# DisplayReceiver_Perpiph.net
KiCad netlist of a schematic drawn in Altium Designer
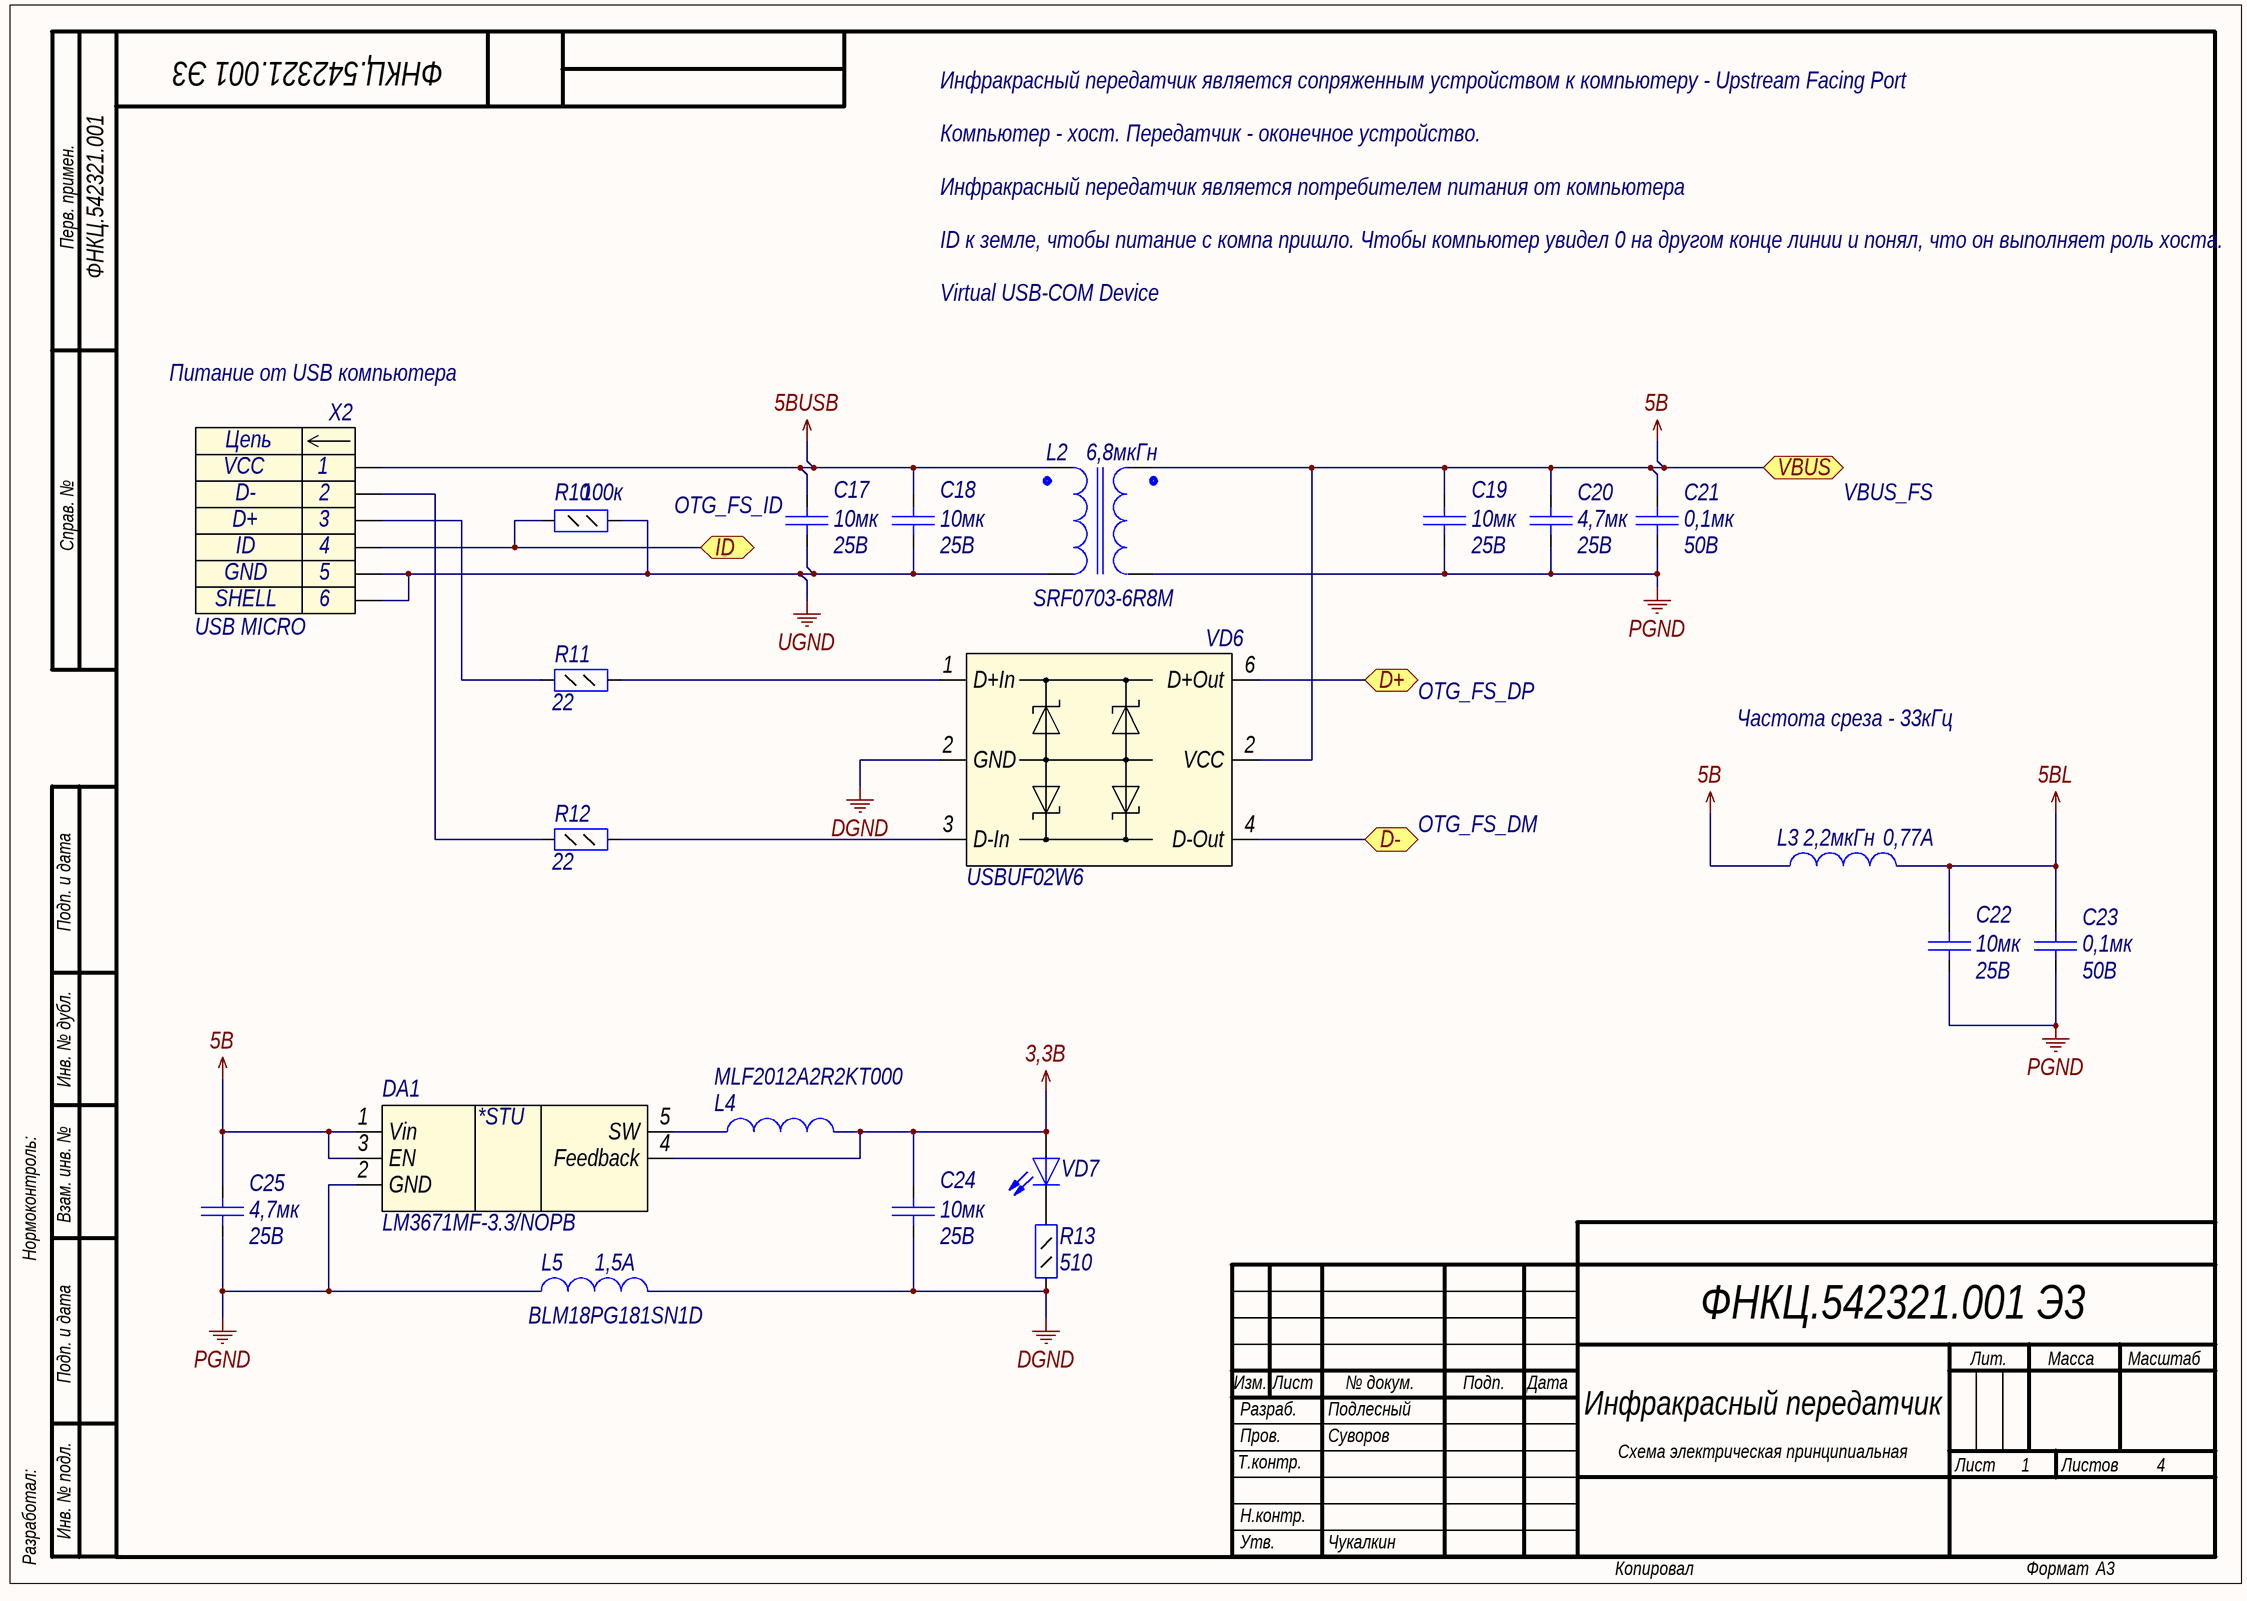
[diagram p0: DisplayReceiver_Perpiph.SchDoc]

(export (version "E")
  (design (tool "Eeschema 10.0.6"))
  (components
    (comp (ref "C17")
      (value "10мк")
      (footprint "C1206")
      (description "Конденсатор")
      (fields
        (field (name "VOLTAGE") "25В")
        (field (name "PART NUMBER") "GRM31CR71E106KA12L*")
        (field (name "Comment") "Capacitor")
      )
      (libsource (lib "MOP44") (part "Capacitor"))
    )
    (comp (ref "C18")
      (value "10мк")
      (footprint "C1206")
      (description "Конденсатор")
      (fields
        (field (name "VOLTAGE") "25В")
        (field (name "PART NUMBER") "GRM31CR71E106KA12L*")
        (field (name "Comment") "Capacitor")
      )
      (libsource (lib "MOP44") (part "Capacitor"))
    )
    (comp (ref "C19")
      (value "10мк")
      (footprint "C1206")
      (description "Конденсатор")
      (fields
        (field (name "VOLTAGE") "25В")
        (field (name "PART NUMBER") "GRM31CR71E106KA12L*")
        (field (name "Comment") "Capacitor")
      )
      (libsource (lib "MOP44") (part "Capacitor"))
    )
    (comp (ref "C20")
      (value "4,7мк")
      (footprint "C0805")
      (description "Конденсатор")
      (fields
        (field (name "VOLTAGE") "25B")
        (field (name "PART NUMBER") "GRM21BR61E475KA12L")
        (field (name "Comment") "Capacitor")
      )
      (libsource (lib "MOP44") (part "Capacitor"))
    )
    (comp (ref "C21")
      (value "0,1мк")
      (footprint "C0805")
      (description "Конденсатор")
      (fields
        (field (name "VOLTAGE") "50B")
        (field (name "PART NUMBER") "GRM21BR71H104K**")
        (field (name "Comment") "Capacitor")
      )
      (libsource (lib "MOP44") (part "Capacitor"))
    )
    (comp (ref "C22")
      (value "10мк")
      (footprint "C1206")
      (description "Конденсатор")
      (fields
        (field (name "VOLTAGE") "25В")
        (field (name "PART NUMBER") "GRM31CR71E106KA12L*")
        (field (name "Comment") "Capacitor")
      )
      (libsource (lib "MOP44") (part "Capacitor"))
    )
    (comp (ref "C23")
      (value "0,1мк")
      (footprint "C0805")
      (description "Конденсатор")
      (fields
        (field (name "VOLTAGE") "50B")
        (field (name "PART NUMBER") "GRM21BR71H104K**")
        (field (name "Comment") "Capacitor")
      )
      (libsource (lib "MOP44") (part "Capacitor"))
    )
    (comp (ref "C24")
      (value "10мк")
      (footprint "C1206")
      (description "Конденсатор")
      (fields
        (field (name "VOLTAGE") "25В")
        (field (name "PART NUMBER") "GRM31CR71E106KA12L*")
        (field (name "Comment") "Capacitor")
      )
      (libsource (lib "MOP44") (part "Capacitor"))
    )
    (comp (ref "C25")
      (value "4,7мк")
      (footprint "C0805")
      (description "Конденсатор")
      (fields
        (field (name "VOLTAGE") "25B")
        (field (name "PART NUMBER") "GRM21BR61E475KA12L")
        (field (name "Comment") "Capacitor")
      )
      (libsource (lib "MOP44") (part "Capacitor"))
    )
    (comp (ref "DA1")
      (value "LM3671MF-3.3/NOPB")
      (footprint "SOT23-5")
      (description "Step-Down DC-DC Converter")
      (fields (field (name "MANUFACTURER") "Texas Instruments"))
      (libsource (lib "MOP44") (part "LM3671MF-3.3/NOPB"))
    )
    (comp (ref "L2")
      (value "6,8мкГн")
      (footprint "SRF0703")
      (description "Синфазный дроссель")
      (fields (field (name "PART NUMBER") "SRF0703-6R8M") (field (name "Comment") "Dual-Winding Inductor"))
      (libsource (lib "MOP44") (part "Dual-Winding Inductor"))
    )
    (comp (ref "L3")
      (value "2,2мкГн")
      (footprint "L1210")
      (description "EMI Suppression Filter")
      (fields
        (field (name "RATED CURRENT") "0,77A")
        (field (name "PART NUMBER") "NLCV32T-2R2M-EF")
        (field (name "Comment") "Inductor")
      )
      (libsource (lib "MOP44") (part "Inductor"))
    )
    (comp (ref "L4")
      (value "Inductor")
      (footprint "L0805")
      (description "EMI Suppression Filter")
      (fields (field (name "PART NUMBER") "MLF2012A2R2KT000"))
      (libsource (lib "MOP44") (part "Inductor"))
    )
    (comp (ref "L5")
      (value "Inductor")
      (footprint "L0603")
      (description "EMI Suppression Filter")
      (fields (field (name "RATED CURRENT") "1,5A") (field (name "PART NUMBER") "BLM18PG181SN1D"))
      (libsource (lib "MOP44") (part "Inductor"))
    )
    (comp (ref "R10")
      (value "100к")
      (footprint "R0805")
      (description "Резистор")
      (fields (field (name "PART NUMBER") "RC0805FR-07100KL") (field (name "POWER") "0,125Вт"))
      (libsource (lib "MOP44") (part "Resistor_0,125Вт"))
    )
    (comp (ref "R11")
      (value "22")
      (footprint "R0805")
      (description "Резистор")
      (fields (field (name "PART NUMBER") "RC0805FR-0722RL") (field (name "POWER") "0,125Вт"))
      (libsource (lib "") (part "Resistor_0,125Вт_1"))
    )
    (comp (ref "R12")
      (value "22")
      (footprint "R0805")
      (description "Резистор")
      (fields (field (name "PART NUMBER") "RC0805FR-0722RL") (field (name "POWER") "0,125Вт"))
      (libsource (lib "") (part "Resistor_0,125Вт_1"))
    )
    (comp (ref "R13")
      (value "510")
      (footprint "R0805")
      (description "Резистор")
      (fields (field (name "PART NUMBER") "RC0805FR-07510RL") (field (name "POWER") "0,125Вт"))
      (libsource (lib "") (part "Resistor_0,125Вт_2"))
    )
    (comp (ref "VD6")
      (value "USBUF")
      (footprint "SOT323-6L")
      (description "EMEMI filter and line termination for USB upstream ports")
      (fields (field (name "PART NUMBER") "USBUF02W6"))
      (libsource (lib "MOP44") (part "USBUF"))
    )
    (comp (ref "VD7")
      (value "LED")
      (footprint "L_0805")
      (description "Светодиод")
      (fields (field (name "PART NUMBER") "KP-2012EC"))
      (libsource (lib "MOP44") (part "LED"))
    )
    (comp (ref "X2")
      (value "USB MICRO")
      (footprint "USB-B Micro")
      (fields (field (name "PART NUMBER") "KLS1-233-0-0-1-T"))
      (libsource (lib "MOP44") (part "USB MICRO"))
    )
  )
  (nets
    (net (code "1") (name "/D+") (class "Default")
      (node (ref "VD6") (pin "6") (pinfunction "D+Out_6") (pintype "passive"))
    )
    (net (code "2") (name "/D-") (class "Default")
      (node (ref "VD6") (pin "4") (pinfunction "D-Out_4") (pintype "passive"))
    )
    (net (code "3") (name "/ID") (class "Default")
      (node (ref "R10") (pin "2") (pinfunction "2_2") (pintype "passive"))
      (node (ref "X2") (pin "4") (pinfunction "4_4") (pintype "passive"))
    )
    (net (code "4") (name "3,3В") (class "Default")
      (node (ref "C24") (pin "2") (pinfunction "2_2") (pintype "passive"))
      (node (ref "DA1") (pin "4") (pinfunction "Feedback_4") (pintype "power_in"))
      (node (ref "L4") (pin "2") (pinfunction "2_2") (pintype "passive"))
      (node (ref "VD7") (pin "2") (pinfunction "A_2") (pintype "passive"))
    )
    (net (code "5") (name "5В") (class "Default")
      (node (ref "C19") (pin "2") (pinfunction "2_2") (pintype "passive"))
      (node (ref "C20") (pin "2") (pinfunction "2_2") (pintype "passive"))
      (node (ref "C21") (pin "2") (pinfunction "2_2") (pintype "passive"))
      (node (ref "C25") (pin "2") (pinfunction "2_2") (pintype "passive"))
      (node (ref "DA1") (pin "1") (pinfunction "Vin_1") (pintype "power_in"))
      (node (ref "DA1") (pin "3") (pinfunction "EN_3") (pintype "power_in"))
      (node (ref "L2") (pin "2") (pintype "passive"))
      (node (ref "L3") (pin "1") (pinfunction "1_1") (pintype "passive"))
      (node (ref "VD6") (pin "2") (pinfunction "VCC_2") (pintype "passive"))
    )
    (net (code "6") (name "5ВL") (class "Default")
      (node (ref "C22") (pin "2") (pinfunction "2_2") (pintype "passive"))
      (node (ref "C23") (pin "2") (pinfunction "2_2") (pintype "passive"))
      (node (ref "L3") (pin "2") (pinfunction "2_2") (pintype "passive"))
    )
    (net (code "7") (name "5ВUSB") (class "Default")
      (node (ref "C17") (pin "2") (pinfunction "2_2") (pintype "passive"))
      (node (ref "C18") (pin "2") (pinfunction "2_2") (pintype "passive"))
      (node (ref "L2") (pin "1") (pintype "passive"))
      (node (ref "X2") (pin "1") (pinfunction "1_1") (pintype "passive"))
    )
    (net (code "8") (name "DGND") (class "Default")
      (node (ref "C24") (pin "1") (pinfunction "1_1") (pintype "passive"))
      (node (ref "L5") (pin "2") (pinfunction "2_2") (pintype "passive"))
      (node (ref "R13") (pin "1") (pinfunction "1_1") (pintype "passive"))
      (node (ref "VD6") (pin "2") (pinfunction "GND_2") (pintype "passive"))
    )
    (net (code "9") (name "Net-(DA1-SW)") (class "Default")
      (node (ref "DA1") (pin "5") (pinfunction "SW_5") (pintype "power_in"))
      (node (ref "L4") (pin "1") (pinfunction "1_1") (pintype "passive"))
    )
    (net (code "10") (name "Net-(R11-Pad1)") (class "Default")
      (node (ref "R11") (pin "1") (pinfunction "1_1") (pintype "passive"))
      (node (ref "X2") (pin "3") (pinfunction "3_3") (pintype "passive"))
    )
    (net (code "11") (name "Net-(R12-Pad1)") (class "Default")
      (node (ref "R12") (pin "1") (pinfunction "1_1") (pintype "passive"))
      (node (ref "X2") (pin "2") (pinfunction "2_2") (pintype "passive"))
    )
    (net (code "12") (name "Net-(VD6-D+In)") (class "Default")
      (node (ref "R11") (pin "2") (pinfunction "2_2") (pintype "passive"))
      (node (ref "VD6") (pin "1") (pinfunction "D+In_1") (pintype "passive"))
    )
    (net (code "13") (name "Net-(VD6-D-In)") (class "Default")
      (node (ref "R12") (pin "2") (pinfunction "2_2") (pintype "passive"))
      (node (ref "VD6") (pin "3") (pinfunction "D-In_3") (pintype "passive"))
    )
    (net (code "14") (name "Net-(VD7-K)") (class "Default")
      (node (ref "R13") (pin "2") (pinfunction "2_2") (pintype "passive"))
      (node (ref "VD7") (pin "1") (pinfunction "K_1") (pintype "passive"))
    )
    (net (code "15") (name "PGND") (class "Default")
      (node (ref "C19") (pin "1") (pinfunction "1_1") (pintype "passive"))
      (node (ref "C20") (pin "1") (pinfunction "1_1") (pintype "passive"))
      (node (ref "C21") (pin "1") (pinfunction "1_1") (pintype "passive"))
      (node (ref "C22") (pin "1") (pinfunction "1_1") (pintype "passive"))
      (node (ref "C23") (pin "1") (pinfunction "1_1") (pintype "passive"))
      (node (ref "C25") (pin "1") (pinfunction "1_1") (pintype "passive"))
      (node (ref "DA1") (pin "2") (pinfunction "GND_2") (pintype "power_in"))
      (node (ref "L2") (pin "4") (pintype "passive"))
      (node (ref "L5") (pin "1") (pinfunction "1_1") (pintype "passive"))
    )
    (net (code "16") (name "UGND") (class "Default")
      (node (ref "C17") (pin "1") (pinfunction "1_1") (pintype "passive"))
      (node (ref "C18") (pin "1") (pinfunction "1_1") (pintype "passive"))
      (node (ref "L2") (pin "3") (pintype "passive"))
      (node (ref "R10") (pin "1") (pinfunction "1_1") (pintype "passive"))
      (node (ref "X2") (pin "5") (pinfunction "5_5") (pintype "passive"))
      (node (ref "X2") (pin "6") (pinfunction "6_6") (pintype "passive"))
    )
  )
)
